# Amazing_All-Band_Receiver.net
KiCad netlist of a schematic drawn in EAGLE
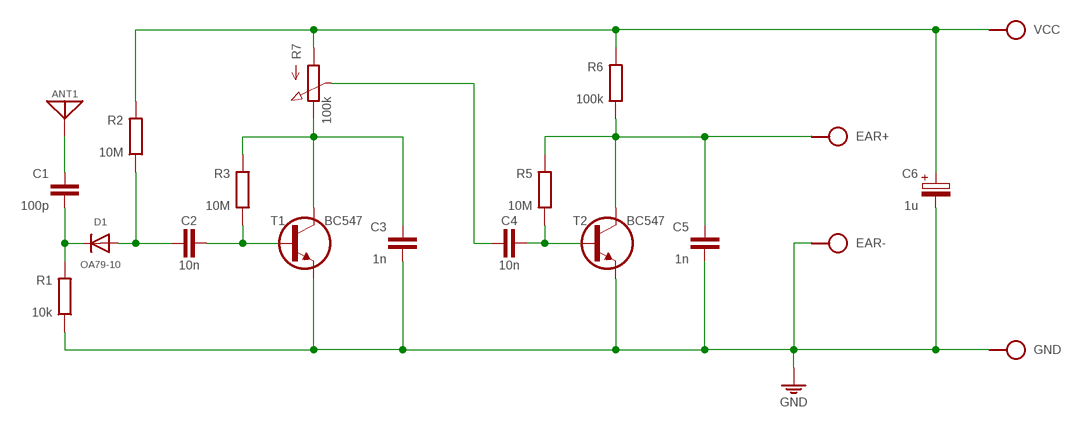
[diagram p0: schematic, sheet 1]

(export (version "E")
  (design (tool "Eeschema 10.0.6"))
  (components
    (comp (ref "ANT1")
      (value "ANT")
      (footprint "eagle-import:SPAD")
      (libsource (lib "eagle-import") (part "ANT"))
    )
    (comp (ref "C1")
      (value "100p")
      (footprint "eagle-import:C050-020X036_V")
      (libsource (lib "eagle-import") (part "C050-020X036/V"))
    )
    (comp (ref "C2")
      (value "10n")
      (footprint "eagle-import:C050-025X075")
      (libsource (lib "eagle-import") (part "C050-025X075"))
    )
    (comp (ref "C3")
      (value "1n")
      (footprint "eagle-import:C050-025X075")
      (libsource (lib "eagle-import") (part "C050-025X075"))
    )
    (comp (ref "C4")
      (value "10n")
      (footprint "eagle-import:C050-025X075")
      (libsource (lib "eagle-import") (part "C050-025X075"))
    )
    (comp (ref "C5")
      (value "1n")
      (footprint "eagle-import:C050-025X075")
      (libsource (lib "eagle-import") (part "C050-025X075"))
    )
    (comp (ref "C6")
      (value "1u")
      (footprint "eagle-import:E2,5-3")
      (libsource (lib "eagle-import") (part "CPOLE2,5-3"))
    )
    (comp (ref "D1")
      (value "OA79-10")
      (footprint "eagle-import:DO34-7V")
      (libsource (lib "eagle-import") (part "1N414834-7V"))
    )
    (comp (ref "EAR+")
      (value "SPAD")
      (footprint "eagle-import:SPAD")
      (libsource (lib "eagle-import") (part "SPAD"))
    )
    (comp (ref "EAR-")
      (value "SPAD")
      (footprint "eagle-import:SPAD")
      (libsource (lib "eagle-import") (part "SPAD"))
    )
    (comp (ref "GND")
      (value "SPAD")
      (footprint "eagle-import:SPAD")
      (libsource (lib "eagle-import") (part "SPAD"))
    )
    (comp (ref "R1")
      (value "10k")
      (footprint "eagle-import:0202_7-V")
      (libsource (lib "eagle-import") (part "R0202/7-V"))
    )
    (comp (ref "R2")
      (value "10M")
      (footprint "eagle-import:0202_7")
      (libsource (lib "eagle-import") (part "R0202/7"))
    )
    (comp (ref "R3")
      (value "10M")
      (footprint "eagle-import:0202_7-V")
      (libsource (lib "eagle-import") (part "R0202/7-V"))
    )
    (comp (ref "R5")
      (value "10M")
      (footprint "eagle-import:0202_7-V")
      (libsource (lib "eagle-import") (part "R0202/7-V"))
    )
    (comp (ref "R6")
      (value "100k")
      (footprint "eagle-import:0202_7-V")
      (libsource (lib "eagle-import") (part "R0202/7-V"))
    )
    (comp (ref "R7")
      (value "100k")
      (footprint "eagle-import:POT")
      (libsource (lib "eagle-import") (part "POT"))
    )
    (comp (ref "T1")
      (value "BC547")
      (footprint "eagle-import:TO92-CBE")
      (libsource (lib "eagle-import") (part "BC547CBE"))
    )
    (comp (ref "T2")
      (value "BC547")
      (footprint "eagle-import:TO92-CBE")
      (libsource (lib "eagle-import") (part "BC547CBE"))
    )
    (comp (ref "VCC")
      (value "SPAD")
      (footprint "eagle-import:SPAD")
      (libsource (lib "eagle-import") (part "SPAD"))
    )
  )
  (nets
    (net (code "1") (name "GND") (class "Default")
      (node (ref "C3") (pin "2") (pinfunction "2_2") (pintype "passive"))
      (node (ref "C5") (pin "2") (pinfunction "2_2") (pintype "passive"))
      (node (ref "C6") (pin "-") (pinfunction "-_-") (pintype "passive"))
      (node (ref "EAR-") (pin "1") (pinfunction "P$1_1") (pintype "bidirectional"))
      (node (ref "GND") (pin "1") (pinfunction "P$1_1") (pintype "bidirectional"))
      (node (ref "R1") (pin "1") (pinfunction "1_1") (pintype "passive"))
      (node (ref "T1") (pin "E") (pinfunction "E_E") (pintype "passive"))
      (node (ref "T2") (pin "E") (pinfunction "E_E") (pintype "passive"))
    )
    (net (code "2") (name "Net-(ANT1-Pad1)") (class "Default")
      (node (ref "ANT1") (pin "1") (pinfunction "1_1") (pintype "output"))
      (node (ref "C1") (pin "1") (pinfunction "1_1") (pintype "passive"))
    )
    (net (code "3") (name "Net-(C1-Pad2)") (class "Default")
      (node (ref "C1") (pin "2") (pinfunction "2_2") (pintype "passive"))
      (node (ref "D1") (pin "C") (pinfunction "C_C") (pintype "passive"))
      (node (ref "R1") (pin "2") (pinfunction "2_2") (pintype "passive"))
    )
    (net (code "4") (name "Net-(C2-Pad1)") (class "Default")
      (node (ref "C2") (pin "1") (pinfunction "1_1") (pintype "passive"))
      (node (ref "R3") (pin "1") (pinfunction "1_1") (pintype "passive"))
      (node (ref "T1") (pin "B") (pinfunction "B_B") (pintype "passive"))
    )
    (net (code "5") (name "Net-(C2-Pad2)") (class "Default")
      (node (ref "C2") (pin "2") (pinfunction "2_2") (pintype "passive"))
      (node (ref "D1") (pin "A") (pinfunction "A_A") (pintype "passive"))
      (node (ref "R2") (pin "1") (pinfunction "1_1") (pintype "passive"))
    )
    (net (code "6") (name "Net-(C4-Pad1)") (class "Default")
      (node (ref "C4") (pin "1") (pinfunction "1_1") (pintype "passive"))
      (node (ref "R5") (pin "1") (pinfunction "1_1") (pintype "passive"))
      (node (ref "T2") (pin "B") (pinfunction "B_B") (pintype "passive"))
    )
    (net (code "7") (name "Net-(EAR+-P$1)") (class "Default")
      (node (ref "C5") (pin "1") (pinfunction "1_1") (pintype "passive"))
      (node (ref "EAR+") (pin "1") (pinfunction "P$1_1") (pintype "bidirectional"))
      (node (ref "R5") (pin "2") (pinfunction "2_2") (pintype "passive"))
      (node (ref "R6") (pin "1") (pinfunction "1_1") (pintype "passive"))
      (node (ref "T2") (pin "C") (pinfunction "C_C") (pintype "passive"))
    )
    (net (code "8") (name "Net-(R7-A)") (class "Default")
      (node (ref "C6") (pin "+") (pinfunction "+_+") (pintype "passive"))
      (node (ref "R2") (pin "2") (pinfunction "2_2") (pintype "passive"))
      (node (ref "R6") (pin "2") (pinfunction "2_2") (pintype "passive"))
      (node (ref "R7") (pin "1") (pinfunction "A_1") (pintype "passive"))
      (node (ref "VCC") (pin "1") (pinfunction "P$1_1") (pintype "bidirectional"))
    )
    (net (code "9") (name "Net-(R7-E)") (class "Default")
      (node (ref "C3") (pin "1") (pinfunction "1_1") (pintype "passive"))
      (node (ref "R3") (pin "2") (pinfunction "2_2") (pintype "passive"))
      (node (ref "R7") (pin "3") (pinfunction "E_3") (pintype "passive"))
      (node (ref "T1") (pin "C") (pinfunction "C_C") (pintype "passive"))
    )
    (net (code "10") (name "Net-(R7-S)") (class "Default")
      (node (ref "C4") (pin "2") (pinfunction "2_2") (pintype "passive"))
      (node (ref "R7") (pin "2") (pinfunction "S_2") (pintype "passive"))
    )
  )
)
